# Sheet1.net
KiCad netlist of a schematic drawn in Altium Designer
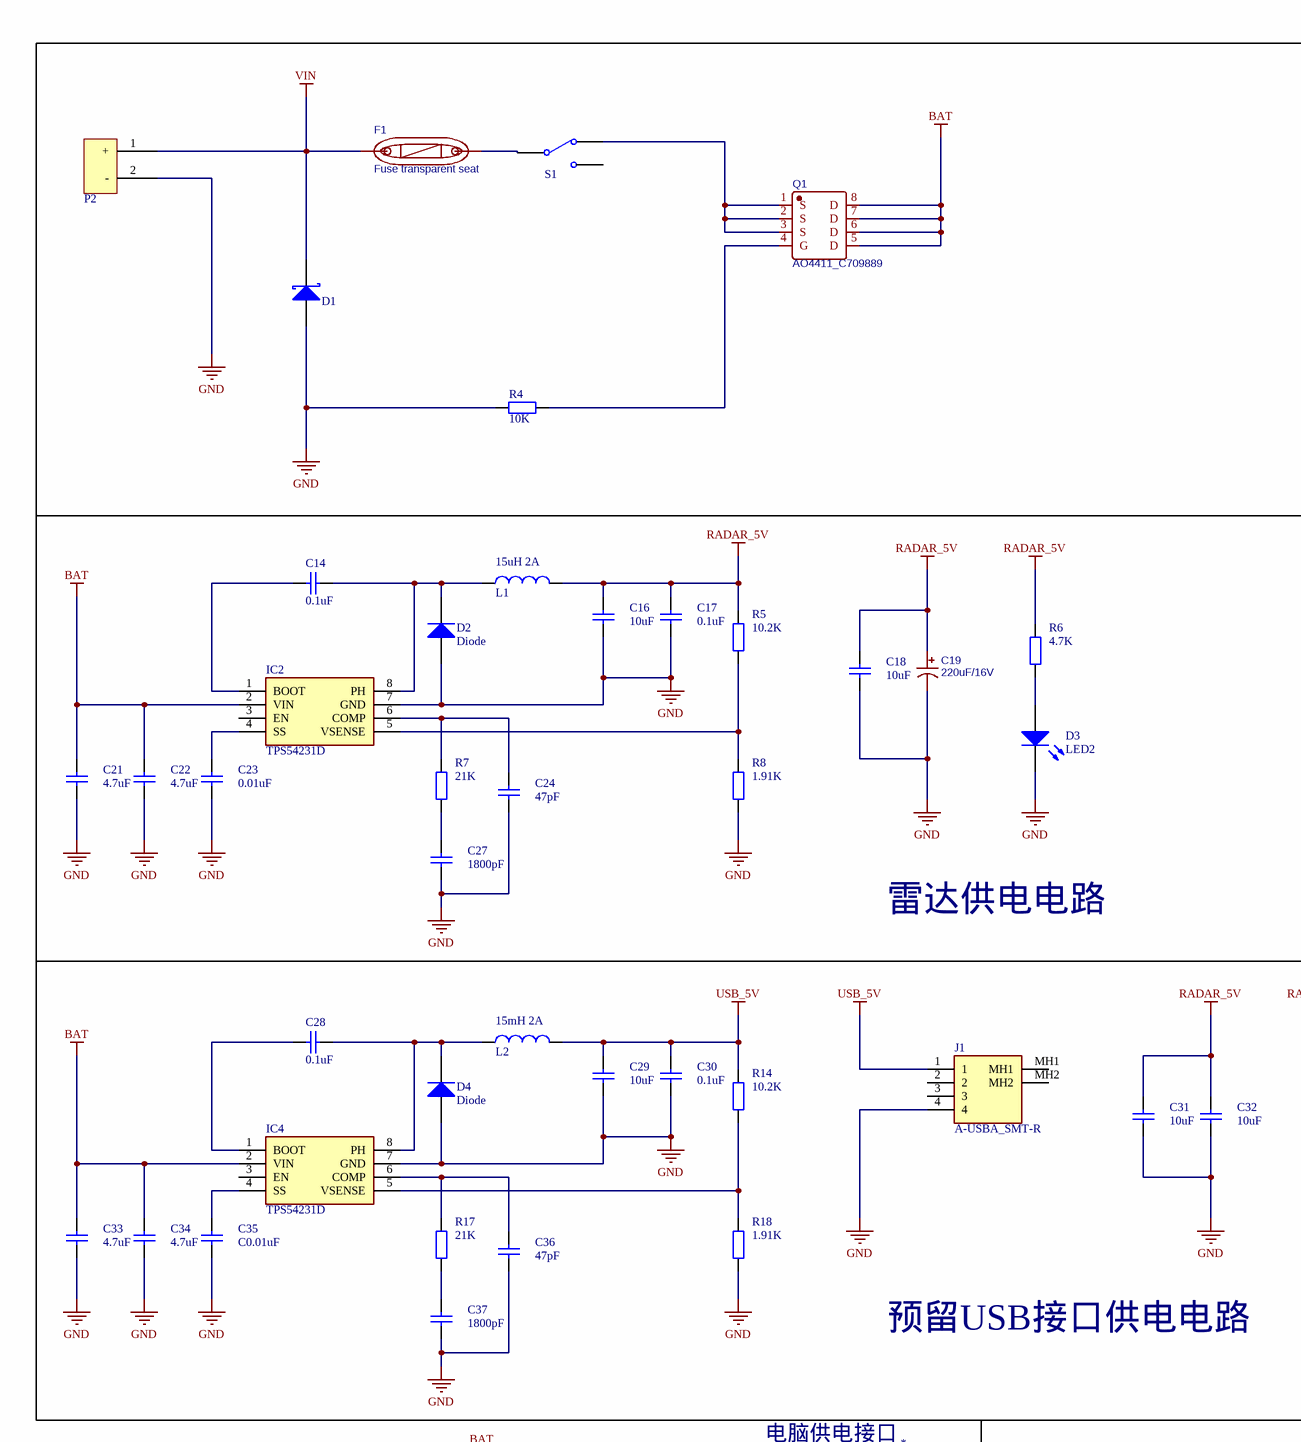
[diagram p0: Sheet1.SchDoc, top left]
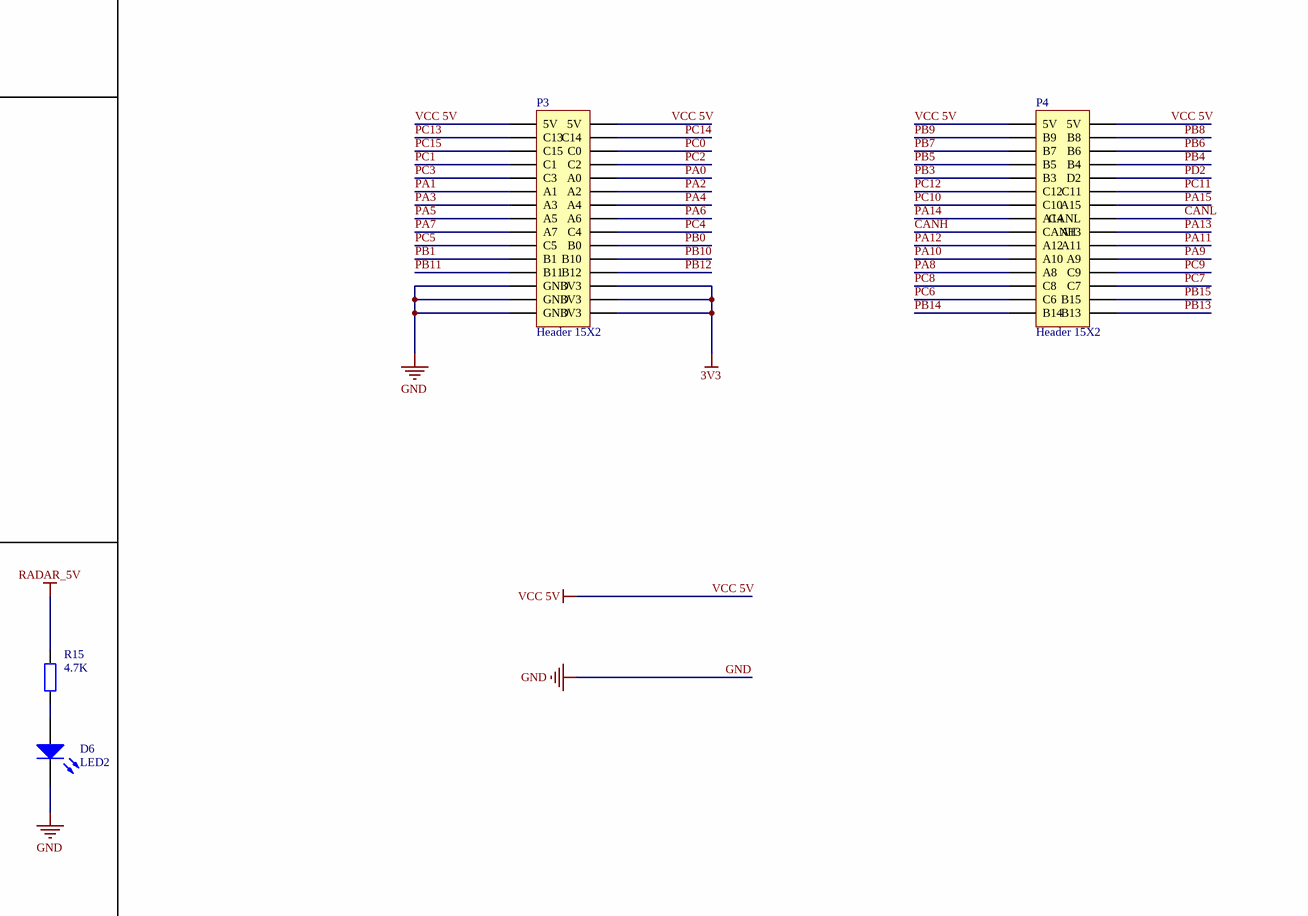
[diagram p1: Sheet1.SchDoc, top middle]
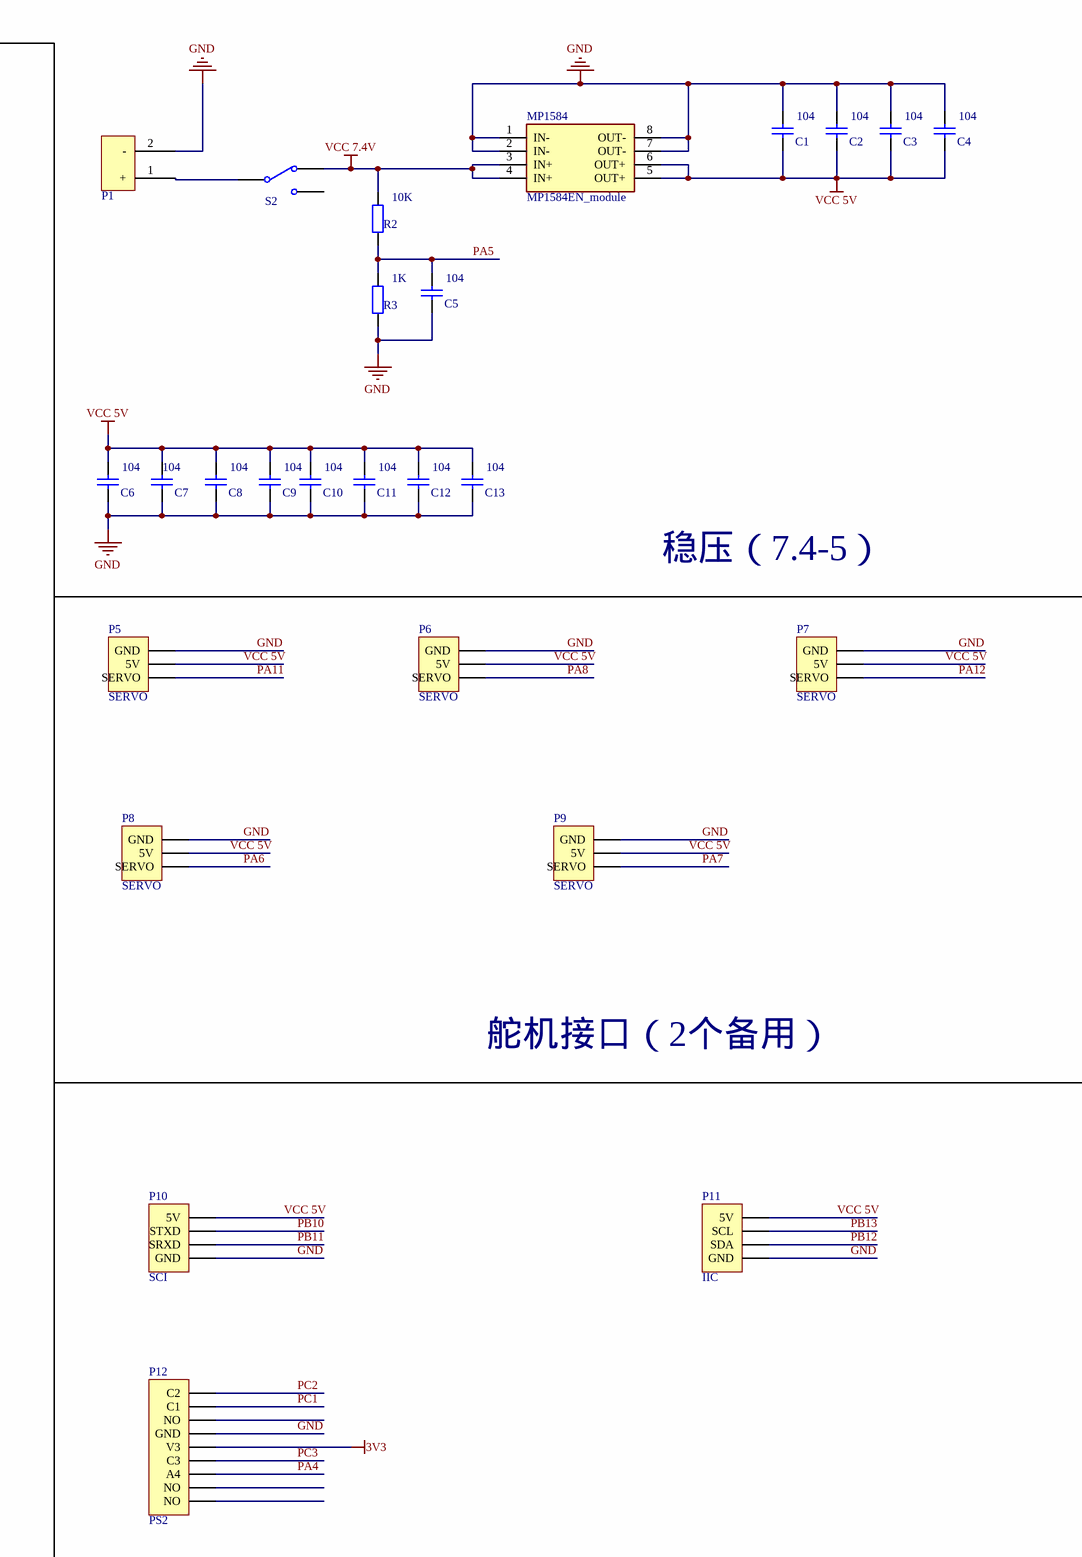
[diagram p2: Sheet1.SchDoc, top right]
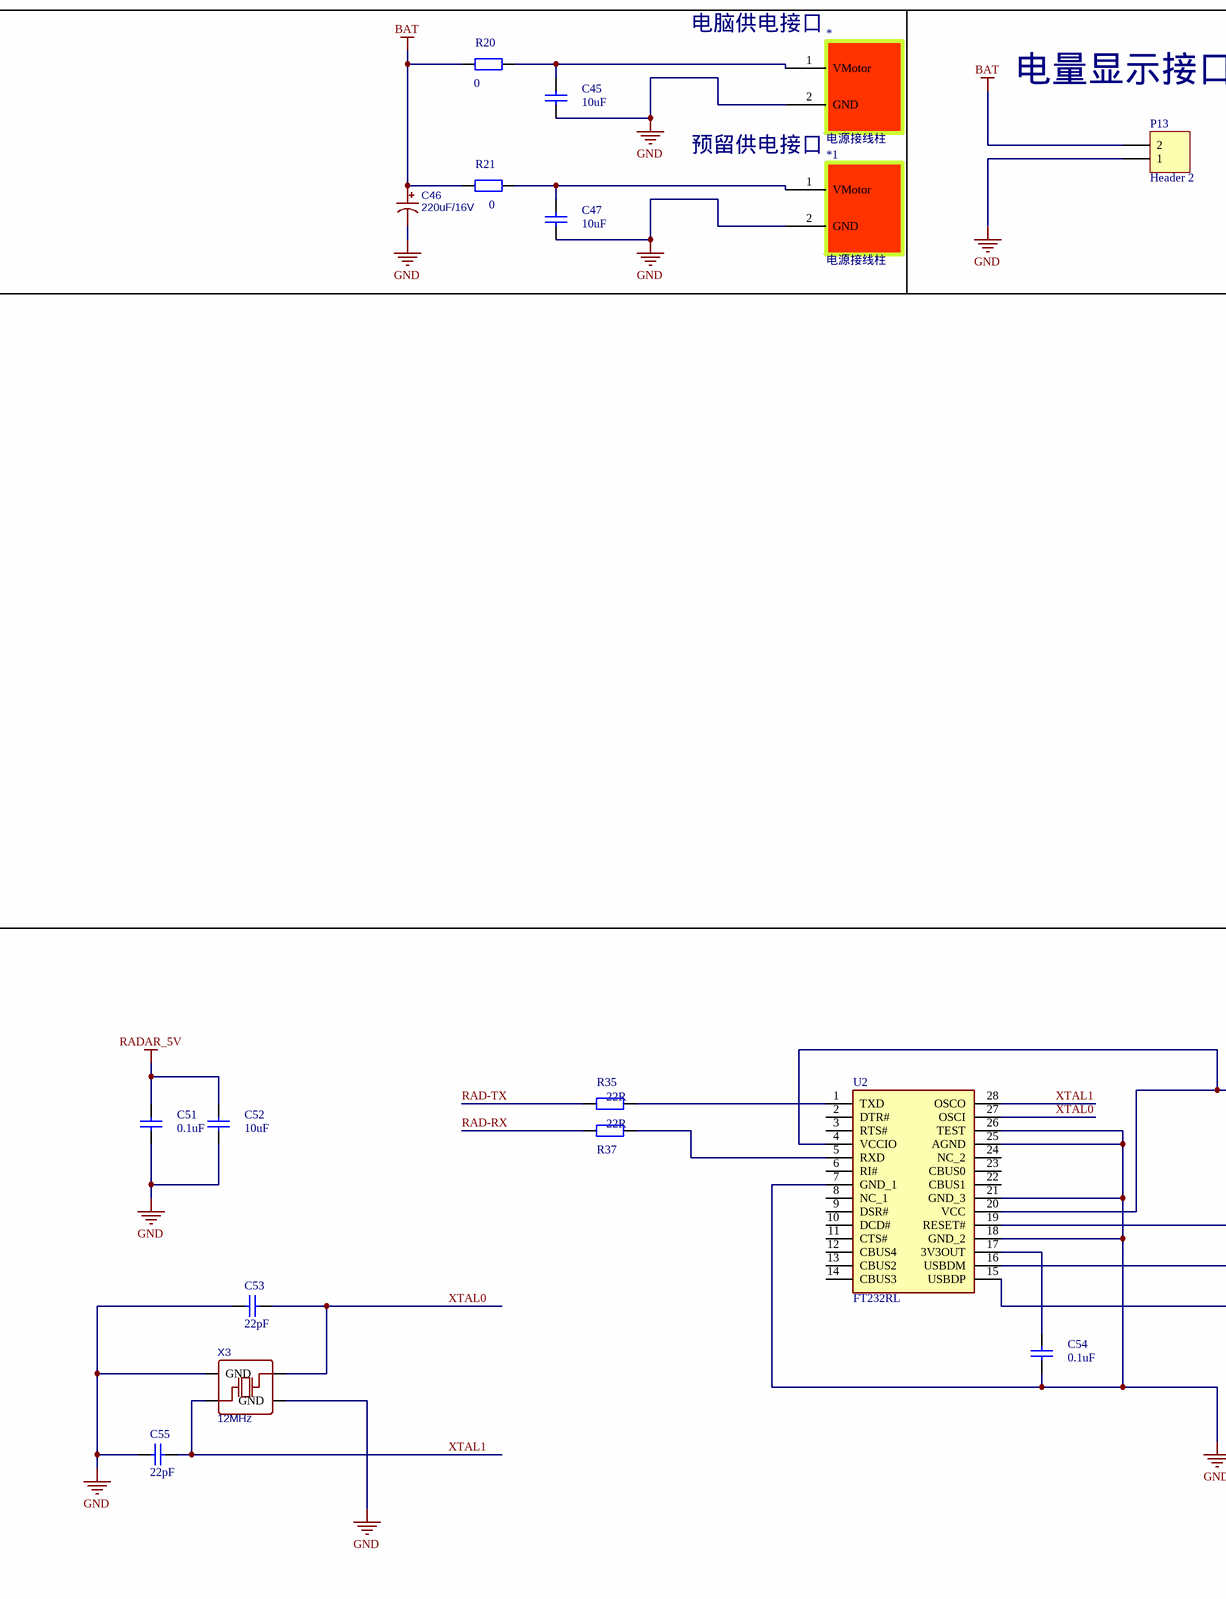
[diagram p3: Sheet1.SchDoc, bottom left]
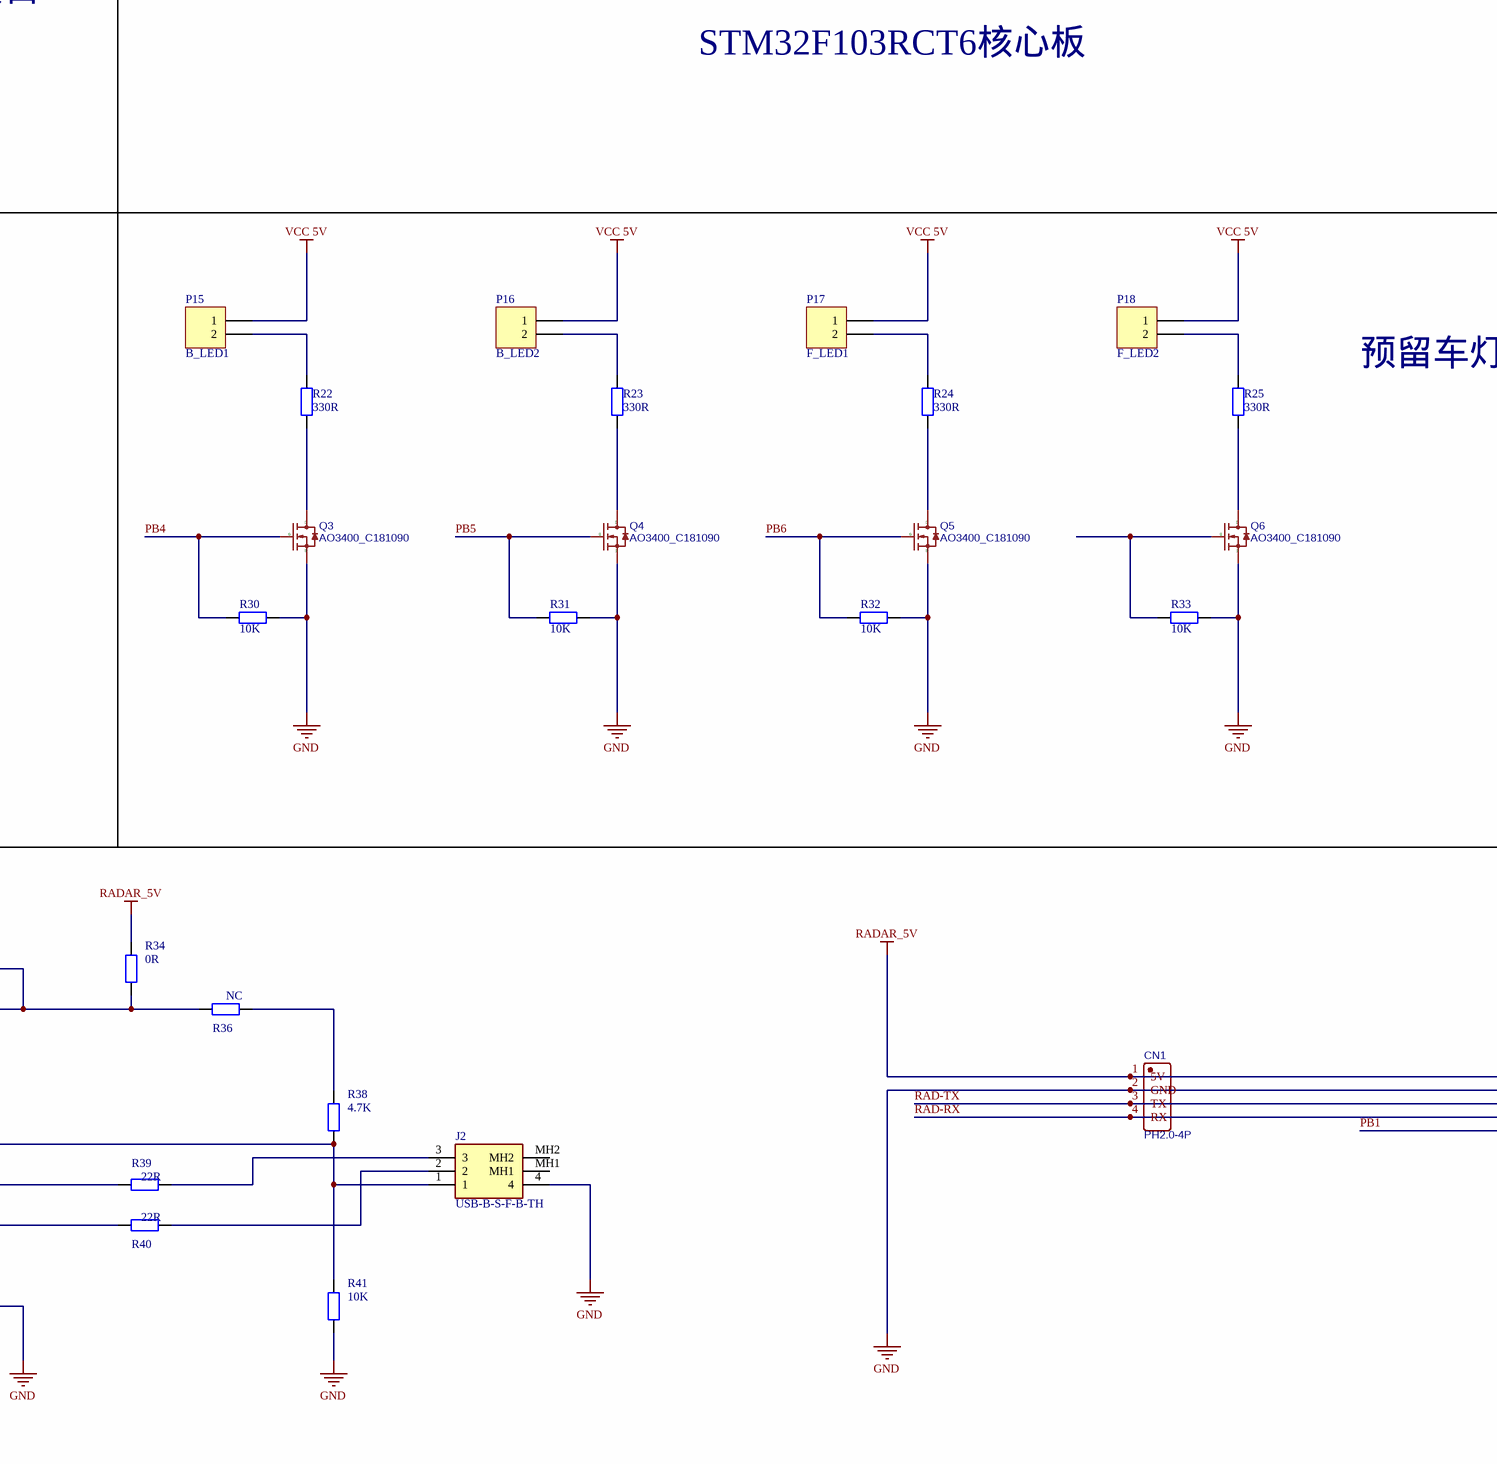
[diagram p4: Sheet1.SchDoc, bottom middle]
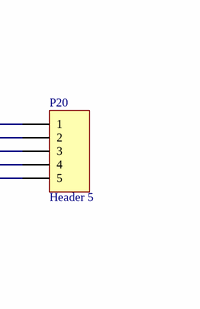
[diagram p5: Sheet1.SchDoc, bottom right]

(export (version "E")
  (design (tool "Eeschema 10.0.6"))
  (components
    (comp (ref "*") (value "电源接线柱") (footprint "接线柱") (libsource (lib "智能车元件") (part "电源接线柱")))
    (comp (ref "*1") (value "电源接线柱") (footprint "接线柱") (libsource (lib "智能车元件") (part "电源接线柱")))
    (comp (ref "C1")
      (value "104")
      (footprint "0805")
      (fields (field (name "PUBLISHER") "Altium Limited"))
      (libsource (lib "智能车元件") (part "C"))
    )
    (comp (ref "C2")
      (value "104")
      (footprint "0805")
      (fields (field (name "PUBLISHER") "Altium Limited"))
      (libsource (lib "智能车元件") (part "C"))
    )
    (comp (ref "C3")
      (value "104")
      (footprint "0805")
      (fields (field (name "PUBLISHER") "Altium Limited"))
      (libsource (lib "智能车元件") (part "C"))
    )
    (comp (ref "C4")
      (value "104")
      (footprint "0805")
      (fields (field (name "PUBLISHER") "Altium Limited"))
      (libsource (lib "智能车元件") (part "C"))
    )
    (comp (ref "C5")
      (value "104")
      (footprint "0805")
      (fields (field (name "PUBLISHER") "Altium Limited"))
      (libsource (lib "智能车元件") (part "C"))
    )
    (comp (ref "C6")
      (value "104")
      (footprint "0805")
      (fields (field (name "PUBLISHER") "Altium Limited"))
      (libsource (lib "智能车元件") (part "C"))
    )
    (comp (ref "C7")
      (value "104")
      (footprint "0805")
      (fields (field (name "PUBLISHER") "Altium Limited"))
      (libsource (lib "智能车元件") (part "C"))
    )
    (comp (ref "C8")
      (value "104")
      (footprint "0805")
      (fields (field (name "PUBLISHER") "Altium Limited"))
      (libsource (lib "智能车元件") (part "C"))
    )
    (comp (ref "C9")
      (value "104")
      (footprint "0805")
      (fields (field (name "PUBLISHER") "Altium Limited"))
      (libsource (lib "智能车元件") (part "C"))
    )
    (comp (ref "C10")
      (value "104")
      (footprint "0805")
      (fields (field (name "PUBLISHER") "Altium Limited"))
      (libsource (lib "智能车元件") (part "C"))
    )
    (comp (ref "C11")
      (value "104")
      (footprint "0805")
      (fields (field (name "PUBLISHER") "Altium Limited"))
      (libsource (lib "智能车元件") (part "C"))
    )
    (comp (ref "C12")
      (value "104")
      (footprint "0805")
      (fields (field (name "PUBLISHER") "Altium Limited"))
      (libsource (lib "智能车元件") (part "C"))
    )
    (comp (ref "C13")
      (value "104")
      (footprint "0805")
      (fields (field (name "PUBLISHER") "Altium Limited"))
      (libsource (lib "智能车元件") (part "C"))
    )
    (comp (ref "C14")
      (value "0.1uF")
      (footprint "0805")
      (fields (field (name "PUBLISHER") "Altium Limited"))
      (libsource (lib "智能车元件") (part "C"))
    )
    (comp (ref "C16")
      (value "10uF")
      (footprint "0805")
      (fields (field (name "PUBLISHER") "Altium Limited"))
      (libsource (lib "智能车元件") (part "C"))
    )
    (comp (ref "C17")
      (value "0.1uF")
      (footprint "0805")
      (fields (field (name "PUBLISHER") "Altium Limited"))
      (libsource (lib "智能车元件") (part "C"))
    )
    (comp (ref "C18")
      (value "10uF")
      (footprint "0805")
      (fields (field (name "PUBLISHER") "Altium Limited"))
      (libsource (lib "智能车元件") (part "C"))
    )
    (comp (ref "C19")
      (value "220uF/16V")
      (footprint "CAP-SMD_BD6.3-L6.6-W6.6-RD")
      (fields
        (field (name "BOM_MANUFACTURER PART") "ZV100M050E055R")
        (field (name "BOM_SUPPLIER PART") "C65228")
      )
      (libsource (lib "CAP_SMD") (part "10uF"))
    )
    (comp (ref "C21")
      (value "4.7uF")
      (footprint "0805")
      (fields (field (name "PUBLISHER") "Altium Limited"))
      (libsource (lib "智能车元件") (part "C"))
    )
    (comp (ref "C22")
      (value "4.7uF")
      (footprint "0805")
      (fields (field (name "PUBLISHER") "Altium Limited"))
      (libsource (lib "智能车元件") (part "C"))
    )
    (comp (ref "C23")
      (value "0.01uF")
      (footprint "0805")
      (fields (field (name "PUBLISHER") "Altium Limited"))
      (libsource (lib "智能车元件") (part "C"))
    )
    (comp (ref "C24")
      (value "47pF")
      (footprint "0805")
      (fields (field (name "PUBLISHER") "Altium Limited"))
      (libsource (lib "智能车元件") (part "C"))
    )
    (comp (ref "C27")
      (value "1800pF")
      (footprint "0805")
      (fields (field (name "PUBLISHER") "Altium Limited"))
      (libsource (lib "智能车元件") (part "C"))
    )
    (comp (ref "C28")
      (value "0.1uF")
      (footprint "0805")
      (fields (field (name "PUBLISHER") "Altium Limited"))
      (libsource (lib "智能车元件") (part "C"))
    )
    (comp (ref "C29")
      (value "10uF")
      (footprint "0805")
      (fields (field (name "PUBLISHER") "Altium Limited"))
      (libsource (lib "智能车元件") (part "C"))
    )
    (comp (ref "C30")
      (value "0.1uF")
      (footprint "0805")
      (fields (field (name "PUBLISHER") "Altium Limited"))
      (libsource (lib "智能车元件") (part "C"))
    )
    (comp (ref "C31")
      (value "10uF")
      (footprint "0805")
      (fields (field (name "PUBLISHER") "Altium Limited"))
      (libsource (lib "智能车元件") (part "C"))
    )
    (comp (ref "C32")
      (value "10uF")
      (footprint "0805")
      (fields (field (name "PUBLISHER") "Altium Limited"))
      (libsource (lib "智能车元件") (part "C"))
    )
    (comp (ref "C33")
      (value "4.7uF")
      (footprint "0805")
      (fields (field (name "PUBLISHER") "Altium Limited"))
      (libsource (lib "智能车元件") (part "C"))
    )
    (comp (ref "C34")
      (value "4.7uF")
      (footprint "0805")
      (fields (field (name "PUBLISHER") "Altium Limited"))
      (libsource (lib "智能车元件") (part "C"))
    )
    (comp (ref "C35")
      (value "C0.01uF")
      (footprint "0805")
      (fields (field (name "PUBLISHER") "Altium Limited"))
      (libsource (lib "智能车元件") (part "C"))
    )
    (comp (ref "C36")
      (value "47pF")
      (footprint "0805")
      (fields (field (name "PUBLISHER") "Altium Limited"))
      (libsource (lib "智能车元件") (part "C"))
    )
    (comp (ref "C37")
      (value "1800pF")
      (footprint "0805")
      (fields (field (name "PUBLISHER") "Altium Limited"))
      (libsource (lib "智能车元件") (part "C"))
    )
    (comp (ref "C45")
      (value "10uF")
      (footprint "0805")
      (fields (field (name "PUBLISHER") "Altium Limited"))
      (libsource (lib "智能车元件") (part "C"))
    )
    (comp (ref "C46")
      (value "220uF/16V")
      (footprint "CAP-SMD_BD6.3-L6.6-W6.6-RD")
      (fields
        (field (name "BOM_MANUFACTURER PART") "ZV100M050E055R")
        (field (name "BOM_SUPPLIER PART") "C65228")
      )
      (libsource (lib "CAP_SMD") (part "10uF"))
    )
    (comp (ref "C47")
      (value "10uF")
      (footprint "0805")
      (fields (field (name "PUBLISHER") "Altium Limited"))
      (libsource (lib "智能车元件") (part "C"))
    )
    (comp (ref "C51")
      (value "0.1uF")
      (footprint "0805")
      (fields (field (name "PUBLISHER") "Altium Limited"))
      (libsource (lib "智能车元件") (part "C"))
    )
    (comp (ref "C52")
      (value "10uF")
      (footprint "0805")
      (fields (field (name "PUBLISHER") "Altium Limited"))
      (libsource (lib "智能车元件") (part "C"))
    )
    (comp (ref "C53")
      (value "22pF")
      (footprint "0805")
      (fields (field (name "PUBLISHER") "Altium Limited"))
      (libsource (lib "智能车元件") (part "C"))
    )
    (comp (ref "C54")
      (value "0.1uF")
      (footprint "0805")
      (fields (field (name "PUBLISHER") "Altium Limited"))
      (libsource (lib "智能车元件") (part "C"))
    )
    (comp (ref "C55")
      (value "22pF")
      (footprint "0805")
      (fields (field (name "PUBLISHER") "Altium Limited"))
      (libsource (lib "智能车元件") (part "C"))
    )
    (comp (ref "CN1")
      (value "PH2.0-4P")
      (footprint "CONN-TH_PH2.0-4P")
      (fields (field (name "BOM_SUPPLIER PART") "C722763") (field (name "CONTRIBUTOR") "LCSC"))
      (libsource (lib "4P-2.0") (part "PH2.0-4P"))
    )
    (comp (ref "D1") (value "D-SS12") (footprint "SMA") (libsource (lib "智能车元件") (part "D-SS12")))
    (comp (ref "D2")
      (value "Diode")
      (footprint "SMC")
      (description "Default Diode")
      (fields (field (name "PUBLISHER") "Altium Limited"))
      (libsource (lib "Miscellaneous Devices") (part "Diode"))
    )
    (comp (ref "D3")
      (value "LED2")
      (footprint "3.2X1.6X1.1")
      (description "Typical RED, GREEN, YELLOW, AMBER GaAs LED")
      (fields (field (name "PUBLISHER") "Altium Limited"))
      (libsource (lib "Miscellaneous Devices") (part "LED2"))
    )
    (comp (ref "D4")
      (value "Diode")
      (footprint "SMC")
      (description "Default Diode")
      (fields (field (name "PUBLISHER") "Altium Limited"))
      (libsource (lib "Miscellaneous Devices") (part "Diode"))
    )
    (comp (ref "D6")
      (value "LED2")
      (footprint "3.2X1.6X1.1")
      (description "Typical RED, GREEN, YELLOW, AMBER GaAs LED")
      (fields (field (name "PUBLISHER") "Altium Limited"))
      (libsource (lib "Miscellaneous Devices") (part "LED2"))
    )
    (comp (ref "F1")
      (value "Fuse transparent seat")
      (footprint "FUSE-TH_L24.5-W9.8-P22.5")
      (fields (field (name "BOM_SUPPLIER PART") "C58066"))
      (libsource (lib "FUSE seat") (part "Fuse transparent seat"))
    )
    (comp (ref "IC2")
      (value "TPS54231D")
      (footprint "CAR1:SOIC127P600X175-8N")
      (description "Integrated Circuit")
      (fields (field (name "MOUSER PART NUMBER") "595-TPS54231D"))
      (libsource (lib "CAR1") (part "TPS54231D"))
    )
    (comp (ref "IC4")
      (value "TPS54231D")
      (footprint "CAR1:SOIC127P600X175-8N")
      (description "Integrated Circuit")
      (fields (field (name "MOUSER PART NUMBER") "595-TPS54231D"))
      (libsource (lib "CAR1") (part "TPS54231D"))
    )
    (comp (ref "J1")
      (value "A-USBA_SMT-R")
      (footprint "CAR1:AUSBASMTR")
      (description "Connector")
      (fields (field (name "MANUFACTURER_PART_NUMBER") "A-USBA/SMT-R"))
      (libsource (lib "CAR1") (part "A-USBA_SMT-R"))
    )
    (comp (ref "J2")
      (value "USB-B-S-F-B-TH")
      (footprint "CAR1:USBBSFBTH")
      (description "Connector")
      (fields (field (name "MOUSER PART NUMBER") "200-USBBSFBTH"))
      (libsource (lib "CAR1") (part "USB-B-S-F-B-TH"))
    )
    (comp (ref "L1") (value "15uH 2A") (footprint "L-7*7") (libsource (lib "智能车元件") (part "L")))
    (comp (ref "L2") (value "15mH 2A") (footprint "L-7*7") (libsource (lib "智能车元件") (part "L")))
    (comp (ref "MP1584")
      (value "MP1584EN_module")
      (footprint "MP1584EN_module")
      (libsource (lib "CAR1") (part "MP1584EN_module"))
    )
    (comp (ref "P1") (value "P") (footprint "T插1") (libsource (lib "") (part "CON-T插_1")))
    (comp (ref "P2") (value "P") (footprint "T插1") (libsource (lib "智能车元件") (part "CON-T插")))
    (comp (ref "P3")
      (value "Header 15X2")
      (footprint "HDR2X15")
      (description "Header, 15-Pin, Dual row")
      (fields (field (name "PUBLISHER") "Altium Limited"))
      (libsource (lib "Miscellaneous Connectors") (part "Header 15X2"))
    )
    (comp (ref "P4")
      (value "Header 15X2")
      (footprint "HDR2X15")
      (description "Header, 15-Pin, Dual row")
      (fields (field (name "PUBLISHER") "Altium Limited"))
      (libsource (lib "Miscellaneous Connectors") (part "Header 15X2"))
    )
    (comp (ref "P5")
      (value "SERVO")
      (footprint "HDR1X3")
      (description "Header, 3-Pin")
      (fields (field (name "PUBLISHER") "Altium Limited"))
      (libsource (lib "Miscellaneous Connectors") (part "Header 3"))
    )
    (comp (ref "P6")
      (value "SERVO")
      (footprint "HDR1X3")
      (description "Header, 3-Pin")
      (fields (field (name "PUBLISHER") "Altium Limited"))
      (libsource (lib "Miscellaneous Connectors") (part "Header 3"))
    )
    (comp (ref "P7")
      (value "SERVO")
      (footprint "HDR1X3")
      (description "Header, 3-Pin")
      (fields (field (name "PUBLISHER") "Altium Limited"))
      (libsource (lib "Miscellaneous Connectors") (part "Header 3"))
    )
    (comp (ref "P8")
      (value "SERVO")
      (footprint "HDR1X3")
      (description "Header, 3-Pin")
      (fields (field (name "PUBLISHER") "Altium Limited"))
      (libsource (lib "Miscellaneous Connectors") (part "Header 3"))
    )
    (comp (ref "P9")
      (value "SERVO")
      (footprint "HDR1X3")
      (description "Header, 3-Pin")
      (fields (field (name "PUBLISHER") "Altium Limited"))
      (libsource (lib "Miscellaneous Connectors") (part "Header 3"))
    )
    (comp (ref "P10")
      (value "SCI")
      (footprint "HDR1X4")
      (description "Header, 4-Pin")
      (fields (field (name "PUBLISHER") "Altium Limited"))
      (libsource (lib "Miscellaneous Connectors") (part "Header 4"))
    )
    (comp (ref "P11")
      (value "IIC")
      (footprint "HDR1X4")
      (description "Header, 4-Pin")
      (fields (field (name "PUBLISHER") "Altium Limited"))
      (libsource (lib "Miscellaneous Connectors") (part "Header 4"))
    )
    (comp (ref "P12")
      (value "PS2")
      (footprint "HDR1X9")
      (description "Header, 9-Pin")
      (fields (field (name "PUBLISHER") "Altium Limited"))
      (libsource (lib "Miscellaneous Connectors") (part "Header 9"))
    )
    (comp (ref "P13")
      (value "Header 2")
      (footprint "HDR1X2")
      (description "Header, 2-Pin")
      (fields (field (name "PUBLISHER") "Altium Limited"))
      (libsource (lib "") (part "Header 2_1"))
    )
    (comp (ref "P15")
      (value "B_LED1")
      (footprint "HDR1X2")
      (description "Header, 2-Pin")
      (fields (field (name "PUBLISHER") "Altium Limited"))
      (libsource (lib "Miscellaneous Connectors") (part "Header 2"))
    )
    (comp (ref "P16")
      (value "B_LED2")
      (footprint "HDR1X2")
      (description "Header, 2-Pin")
      (fields (field (name "PUBLISHER") "Altium Limited"))
      (libsource (lib "Miscellaneous Connectors") (part "Header 2"))
    )
    (comp (ref "P17")
      (value "F_LED1")
      (footprint "HDR1X2")
      (description "Header, 2-Pin")
      (fields (field (name "PUBLISHER") "Altium Limited"))
      (libsource (lib "Miscellaneous Connectors") (part "Header 2"))
    )
    (comp (ref "P18")
      (value "F_LED2")
      (footprint "HDR1X2")
      (description "Header, 2-Pin")
      (fields (field (name "PUBLISHER") "Altium Limited"))
      (libsource (lib "Miscellaneous Connectors") (part "Header 2"))
    )
    (comp (ref "P20")
      (value "Header 5")
      (footprint "HDR1X5")
      (description "Header, 5-Pin")
      (fields (field (name "PUBLISHER") "Altium Limited"))
      (libsource (lib "Miscellaneous Connectors") (part "Header 5"))
    )
    (comp (ref "Q1")
      (value "AO4411_C709889")
      (footprint "SO-8_L4.9-W3.9-P1.27-LS5.9-BL")
      (fields
        (field (name "BOM_SUPPLIER PART") "C709889")
        (field (name "BOM_MANUFACTURER PART") "AO4411")
        (field (name "CONTRIBUTOR") "LCSC")
      )
      (libsource (lib "AO4411") (part "AO4411_C709889"))
    )
    (comp (ref "Q3")
      (value "AO3400_C181090")
      (footprint "SOT-23-3_L2.9-W1.3-P1.90-LS2.4-BR")
      (fields
        (field (name "BOM_MANUFACTURER PART") "AO3400")
        (field (name "BOM_SUPPLIER PART") "C181090")
        (field (name "CONTRIBUTOR") "LCSC")
      )
      (libsource (lib "Free Documents") (part "AO3400_C181090"))
    )
    (comp (ref "Q4")
      (value "AO3400_C181090")
      (footprint "SOT-23-3_L2.9-W1.3-P1.90-LS2.4-BR")
      (fields
        (field (name "BOM_MANUFACTURER PART") "AO3400")
        (field (name "BOM_SUPPLIER PART") "C181090")
        (field (name "CONTRIBUTOR") "LCSC")
      )
      (libsource (lib "Free Documents") (part "AO3400_C181090"))
    )
    (comp (ref "Q5")
      (value "AO3400_C181090")
      (footprint "SOT-23-3_L2.9-W1.3-P1.90-LS2.4-BR")
      (fields
        (field (name "BOM_MANUFACTURER PART") "AO3400")
        (field (name "BOM_SUPPLIER PART") "C181090")
        (field (name "CONTRIBUTOR") "LCSC")
      )
      (libsource (lib "Free Documents") (part "AO3400_C181090"))
    )
    (comp (ref "Q6")
      (value "AO3400_C181090")
      (footprint "SOT-23-3_L2.9-W1.3-P1.90-LS2.4-BR")
      (fields
        (field (name "BOM_MANUFACTURER PART") "AO3400")
        (field (name "BOM_SUPPLIER PART") "C181090")
        (field (name "CONTRIBUTOR") "LCSC")
      )
      (libsource (lib "Free Documents") (part "AO3400_C181090"))
    )
    (comp (ref "R2") (value "10K") (footprint "0805") (libsource (lib "") (part "R_1")))
    (comp (ref "R3") (value "1K") (footprint "0805") (libsource (lib "") (part "R_1")))
    (comp (ref "R4") (value "10K") (footprint "0805") (libsource (lib "") (part "R_3")))
    (comp (ref "R5") (value "10.2K") (footprint "0805") (libsource (lib "") (part "R_1")))
    (comp (ref "R6") (value "4.7K") (footprint "0805") (libsource (lib "") (part "R_1")))
    (comp (ref "R7") (value "21K") (footprint "0805") (libsource (lib "") (part "R_1")))
    (comp (ref "R8") (value "1.91K") (footprint "0805") (libsource (lib "") (part "R_1")))
    (comp (ref "R14") (value "10.2K") (footprint "0805") (libsource (lib "") (part "R_1")))
    (comp (ref "R15") (value "4.7K") (footprint "0805") (libsource (lib "") (part "R_1")))
    (comp (ref "R17") (value "21K") (footprint "0805") (libsource (lib "") (part "R_1")))
    (comp (ref "R18") (value "1.91K") (footprint "0805") (libsource (lib "") (part "R_1")))
    (comp (ref "R20") (value "0") (footprint "0805") (libsource (lib "智能车元件") (part "R")))
    (comp (ref "R21") (value "0") (footprint "0805") (libsource (lib "智能车元件") (part "R")))
    (comp (ref "R22") (value "330R") (footprint "0805") (libsource (lib "") (part "R_2")))
    (comp (ref "R23") (value "330R") (footprint "0805") (libsource (lib "") (part "R_2")))
    (comp (ref "R24") (value "330R") (footprint "0805") (libsource (lib "") (part "R_2")))
    (comp (ref "R25") (value "330R") (footprint "0805") (libsource (lib "") (part "R_2")))
    (comp (ref "R30") (value "10K") (footprint "0805") (libsource (lib "智能车元件") (part "R")))
    (comp (ref "R31") (value "10K") (footprint "0805") (libsource (lib "智能车元件") (part "R")))
    (comp (ref "R32") (value "10K") (footprint "0805") (libsource (lib "智能车元件") (part "R")))
    (comp (ref "R33") (value "10K") (footprint "0805") (libsource (lib "智能车元件") (part "R")))
    (comp (ref "R34") (value "0R") (footprint "0805") (libsource (lib "") (part "R_1")))
    (comp (ref "R35") (value "22R") (footprint "0805") (libsource (lib "智能车元件") (part "R")))
    (comp (ref "R36") (value "NC") (footprint "0805") (libsource (lib "智能车元件") (part "R")))
    (comp (ref "R37") (value "22R") (footprint "0805") (libsource (lib "智能车元件") (part "R")))
    (comp (ref "R38") (value "4.7K") (footprint "0805") (libsource (lib "") (part "R_1")))
    (comp (ref "R39") (value "22R") (footprint "0805") (libsource (lib "智能车元件") (part "R")))
    (comp (ref "R40") (value "22R") (footprint "0805") (libsource (lib "智能车元件") (part "R")))
    (comp (ref "R41") (value "10K") (footprint "0805") (libsource (lib "") (part "R_1")))
    (comp (ref "S1") (value "SWITCH") (footprint "纽子开关") (libsource (lib "智能车元件") (part "SW-钮子开关")))
    (comp (ref "S2") (value "SWITCH") (footprint "纽子开关") (libsource (lib "智能车元件") (part "SW-钮子开关")))
    (comp (ref "U2")
      (value "FT232RL")
      (footprint "CAR1:SOP65P778X200-28N")
      (description "Integrated Circuit")
      (libsource (lib "CAR1") (part "FT232RL"))
    )
    (comp (ref "X3")
      (value "12MHz")
      (footprint "OSC-SMD_4P-L3.2-W2.5-BL")
      (fields
        (field (name "BOM_SUPPLIER PART") "C258939")
        (field (name "BOM_MANUFACTURER PART") "M12000J134")
        (field (name "CONTRIBUTOR") "LCSC")
      )
      (libsource (lib "Free Documents") (part "12MHz"))
    )
  )
  (nets
    (net (code "1") (name "/CANH") (class "Default")
      (node (ref "P4") (pin "17") (pinfunction "A7_17") (pintype "passive"))
    )
    (net (code "2") (name "/CANL") (class "Default")
      (node (ref "P4") (pin "16") (pinfunction "A6_16") (pintype "passive"))
    )
    (net (code "3") (name "/PA0") (class "Default")
      (node (ref "P3") (pin "10") (pinfunction "A0_10") (pintype "passive"))
    )
    (net (code "4") (name "/PA1") (class "Default")
      (node (ref "P3") (pin "11") (pinfunction "A1_11") (pintype "passive"))
    )
    (net (code "5") (name "/PA2") (class "Default")
      (node (ref "P3") (pin "12") (pinfunction "A2_12") (pintype "passive"))
    )
    (net (code "6") (name "/PA3") (class "Default")
      (node (ref "P3") (pin "13") (pinfunction "A3_13") (pintype "passive"))
    )
    (net (code "7") (name "/PA4") (class "Default")
      (node (ref "P12") (pin "7") (pinfunction "A4_7") (pintype "passive"))
      (node (ref "P3") (pin "14") (pinfunction "A4_14") (pintype "passive"))
    )
    (net (code "8") (name "/PA5") (class "Default")
      (node (ref "C5") (pin "2") (pinfunction "2_2") (pintype "passive"))
      (node (ref "P3") (pin "15") (pinfunction "A5_15") (pintype "passive"))
      (node (ref "R2") (pin "1") (pinfunction "1_1") (pintype "passive"))
      (node (ref "R3") (pin "2") (pinfunction "2_2") (pintype "passive"))
    )
    (net (code "9") (name "/PA6") (class "Default")
      (node (ref "P3") (pin "16") (pinfunction "A6_16") (pintype "passive"))
      (node (ref "P8") (pin "3") (pinfunction "SERVO_3") (pintype "passive"))
    )
    (net (code "10") (name "/PA7") (class "Default")
      (node (ref "P3") (pin "17") (pinfunction "A7_17") (pintype "passive"))
      (node (ref "P9") (pin "3") (pinfunction "SERVO_3") (pintype "passive"))
    )
    (net (code "11") (name "/PA8") (class "Default")
      (node (ref "P4") (pin "23") (pinfunction "B11_23") (pintype "passive"))
      (node (ref "P6") (pin "3") (pinfunction "SERVO_3") (pintype "passive"))
    )
    (net (code "12") (name "/PA9") (class "Default")
      (node (ref "P4") (pin "22") (pinfunction "B10_22") (pintype "passive"))
    )
    (net (code "13") (name "/PA10") (class "Default")
      (node (ref "P4") (pin "21") (pinfunction "B1_21") (pintype "passive"))
    )
    (net (code "14") (name "/PA11") (class "Default")
      (node (ref "P4") (pin "20") (pinfunction "B0_20") (pintype "passive"))
      (node (ref "P5") (pin "3") (pinfunction "SERVO_3") (pintype "passive"))
    )
    (net (code "15") (name "/PA12") (class "Default")
      (node (ref "P4") (pin "19") (pinfunction "C5_19") (pintype "passive"))
      (node (ref "P7") (pin "3") (pinfunction "SERVO_3") (pintype "passive"))
    )
    (net (code "16") (name "/PA13") (class "Default")
      (node (ref "P4") (pin "18") (pinfunction "C4_18") (pintype "passive"))
    )
    (net (code "17") (name "/PA14") (class "Default")
      (node (ref "P4") (pin "15") (pinfunction "A5_15") (pintype "passive"))
    )
    (net (code "18") (name "/PA15") (class "Default")
      (node (ref "P4") (pin "14") (pinfunction "A4_14") (pintype "passive"))
    )
    (net (code "19") (name "/PB0") (class "Default")
      (node (ref "P3") (pin "20") (pinfunction "B0_20") (pintype "passive"))
    )
    (net (code "20") (name "/PB1") (class "Default")
      (node (ref "P20") (pin "5") (pinfunction "5_5") (pintype "passive"))
      (node (ref "P3") (pin "21") (pinfunction "B1_21") (pintype "passive"))
    )
    (net (code "21") (name "/PB3") (class "Default")
      (node (ref "P4") (pin "9") (pinfunction "C3_9") (pintype "passive"))
    )
    (net (code "22") (name "/PB4") (class "Default")
      (node (ref "P4") (pin "8") (pinfunction "C2_8") (pintype "passive"))
      (node (ref "Q3") (pin "1") (pinfunction "G_1") (pintype "passive"))
      (node (ref "R30") (pin "1") (pinfunction "1_1") (pintype "passive"))
    )
    (net (code "23") (name "/PB5") (class "Default")
      (node (ref "P4") (pin "7") (pinfunction "C1_7") (pintype "passive"))
      (node (ref "Q4") (pin "1") (pinfunction "G_1") (pintype "passive"))
      (node (ref "R31") (pin "1") (pinfunction "1_1") (pintype "passive"))
    )
    (net (code "24") (name "/PB6") (class "Default")
      (node (ref "P4") (pin "6") (pinfunction "C0_6") (pintype "passive"))
      (node (ref "Q5") (pin "1") (pinfunction "G_1") (pintype "passive"))
      (node (ref "R32") (pin "1") (pinfunction "1_1") (pintype "passive"))
    )
    (net (code "25") (name "/PB7") (class "Default")
      (node (ref "P4") (pin "5") (pinfunction "C15_5") (pintype "passive"))
    )
    (net (code "26") (name "/PB8") (class "Default")
      (node (ref "P4") (pin "4") (pinfunction "C14_4") (pintype "passive"))
    )
    (net (code "27") (name "/PB9") (class "Default")
      (node (ref "P4") (pin "3") (pinfunction "C13_3") (pintype "passive"))
    )
    (net (code "28") (name "/PB10") (class "Default")
      (node (ref "P10") (pin "2") (pinfunction "SCL_2") (pintype "passive"))
      (node (ref "P3") (pin "22") (pinfunction "B10_22") (pintype "passive"))
    )
    (net (code "29") (name "/PB11") (class "Default")
      (node (ref "P10") (pin "3") (pinfunction "SDA_3") (pintype "passive"))
      (node (ref "P3") (pin "23") (pinfunction "B11_23") (pintype "passive"))
    )
    (net (code "30") (name "/PB12") (class "Default")
      (node (ref "P11") (pin "3") (pinfunction "SDA_3") (pintype "passive"))
      (node (ref "P3") (pin "24") (pinfunction "B12_24") (pintype "passive"))
    )
    (net (code "31") (name "/PB13") (class "Default")
      (node (ref "P11") (pin "2") (pinfunction "SCL_2") (pintype "passive"))
      (node (ref "P4") (pin "30") (pinfunction "3V3_30") (pintype "passive"))
    )
    (net (code "32") (name "/PB14") (class "Default")
      (node (ref "P4") (pin "29") (pinfunction "GND_29") (pintype "passive"))
    )
    (net (code "33") (name "/PB15") (class "Default")
      (node (ref "P4") (pin "28") (pinfunction "3V3_28") (pintype "passive"))
    )
    (net (code "34") (name "/PC0") (class "Default")
      (node (ref "P3") (pin "6") (pinfunction "C0_6") (pintype "passive"))
    )
    (net (code "35") (name "/PC1") (class "Default")
      (node (ref "P12") (pin "2") (pinfunction "C1_2") (pintype "passive"))
      (node (ref "P3") (pin "7") (pinfunction "C1_7") (pintype "passive"))
    )
    (net (code "36") (name "/PC2") (class "Default")
      (node (ref "P12") (pin "1") (pinfunction "C2_1") (pintype "passive"))
      (node (ref "P3") (pin "8") (pinfunction "C2_8") (pintype "passive"))
    )
    (net (code "37") (name "/PC3") (class "Default")
      (node (ref "P12") (pin "6") (pinfunction "C3_6") (pintype "passive"))
      (node (ref "P3") (pin "9") (pinfunction "C3_9") (pintype "passive"))
    )
    (net (code "38") (name "/PC4") (class "Default")
      (node (ref "P3") (pin "18") (pinfunction "C4_18") (pintype "passive"))
    )
    (net (code "39") (name "/PC5") (class "Default")
      (node (ref "P3") (pin "19") (pinfunction "C5_19") (pintype "passive"))
    )
    (net (code "40") (name "/PC6") (class "Default")
      (node (ref "P4") (pin "27") (pinfunction "GND_27") (pintype "passive"))
    )
    (net (code "41") (name "/PC7") (class "Default")
      (node (ref "P4") (pin "26") (pinfunction "3V3_26") (pintype "passive"))
    )
    (net (code "42") (name "/PC8") (class "Default")
      (node (ref "P4") (pin "25") (pinfunction "GND_25") (pintype "passive"))
    )
    (net (code "43") (name "/PC9") (class "Default")
      (node (ref "P4") (pin "24") (pinfunction "B12_24") (pintype "passive"))
    )
    (net (code "44") (name "/PC10") (class "Default")
      (node (ref "P4") (pin "13") (pinfunction "A3_13") (pintype "passive"))
    )
    (net (code "45") (name "/PC11") (class "Default")
      (node (ref "P4") (pin "12") (pinfunction "A2_12") (pintype "passive"))
    )
    (net (code "46") (name "/PC12") (class "Default")
      (node (ref "P4") (pin "11") (pinfunction "A1_11") (pintype "passive"))
    )
    (net (code "47") (name "/PC13") (class "Default")
      (node (ref "P3") (pin "3") (pinfunction "C13_3") (pintype "passive"))
    )
    (net (code "48") (name "/PC14") (class "Default")
      (node (ref "P3") (pin "4") (pinfunction "C14_4") (pintype "passive"))
    )
    (net (code "49") (name "/PC15") (class "Default")
      (node (ref "P3") (pin "5") (pinfunction "C15_5") (pintype "passive"))
    )
    (net (code "50") (name "/PD2") (class "Default")
      (node (ref "P4") (pin "10") (pinfunction "A0_10") (pintype "passive"))
    )
    (net (code "51") (name "/RAD-RX") (class "Default")
      (node (ref "CN1") (pin "4") (pinfunction "RX_4") (pintype "passive"))
      (node (ref "P20") (pin "4") (pinfunction "4_4") (pintype "passive"))
      (node (ref "R37") (pin "1") (pinfunction "1_1") (pintype "passive"))
    )
    (net (code "52") (name "/RAD-TX") (class "Default")
      (node (ref "CN1") (pin "3") (pinfunction "TX_3") (pintype "passive"))
      (node (ref "P20") (pin "3") (pinfunction "3_3") (pintype "passive"))
      (node (ref "R35") (pin "1") (pinfunction "1_1") (pintype "passive"))
    )
    (net (code "53") (name "/XTAL0") (class "Default")
      (node (ref "C53") (pin "1") (pinfunction "1_1") (pintype "passive"))
      (node (ref "U2") (pin "27") (pinfunction "OSCI_27") (pintype "passive"))
      (node (ref "X3") (pin "3") (pinfunction "OSC2_3") (pintype "passive"))
    )
    (net (code "54") (name "/XTAL1") (class "Default")
      (node (ref "C55") (pin "1") (pinfunction "1_1") (pintype "passive"))
      (node (ref "U2") (pin "28") (pinfunction "OSCO_28") (pintype "passive"))
      (node (ref "X3") (pin "1") (pinfunction "OSC1_1") (pintype "passive"))
    )
    (net (code "55") (name "3V3") (class "Default")
      (node (ref "P12") (pin "5") (pinfunction "V3_5") (pintype "passive"))
      (node (ref "P3") (pin "26") (pinfunction "3V3_26") (pintype "passive"))
      (node (ref "P3") (pin "28") (pinfunction "3V3_28") (pintype "passive"))
      (node (ref "P3") (pin "30") (pinfunction "3V3_30") (pintype "passive"))
    )
    (net (code "56") (name "BAT") (class "Default")
      (node (ref "C21") (pin "2") (pinfunction "2_2") (pintype "passive"))
      (node (ref "C22") (pin "2") (pinfunction "2_2") (pintype "passive"))
      (node (ref "C33") (pin "2") (pinfunction "2_2") (pintype "passive"))
      (node (ref "C34") (pin "2") (pinfunction "2_2") (pintype "passive"))
      (node (ref "C46") (pin "1") (pinfunction "1_1") (pintype "passive"))
      (node (ref "IC2") (pin "2") (pinfunction "VIN_2") (pintype "passive"))
      (node (ref "IC4") (pin "2") (pinfunction "VIN_2") (pintype "passive"))
      (node (ref "P13") (pin "2") (pinfunction "2_2") (pintype "passive"))
      (node (ref "Q1") (pin "5") (pinfunction "D_5") (pintype "passive"))
      (node (ref "Q1") (pin "6") (pinfunction "D_6") (pintype "passive"))
      (node (ref "Q1") (pin "7") (pinfunction "D_7") (pintype "passive"))
      (node (ref "Q1") (pin "8") (pinfunction "D_8") (pintype "passive"))
      (node (ref "R20") (pin "1") (pinfunction "1_1") (pintype "passive"))
      (node (ref "R21") (pin "1") (pinfunction "1_1") (pintype "passive"))
    )
    (net (code "57") (name "GND") (class "Default")
      (node (ref "*") (pin "2") (pinfunction "GND_2") (pintype "passive"))
      (node (ref "*1") (pin "2") (pinfunction "GND_2") (pintype "passive"))
      (node (ref "C1") (pin "2") (pinfunction "2_2") (pintype "passive"))
      (node (ref "C10") (pin "1") (pinfunction "1_1") (pintype "passive"))
      (node (ref "C11") (pin "1") (pinfunction "1_1") (pintype "passive"))
      (node (ref "C12") (pin "1") (pinfunction "1_1") (pintype "passive"))
      (node (ref "C13") (pin "1") (pinfunction "1_1") (pintype "passive"))
      (node (ref "C16") (pin "1") (pinfunction "1_1") (pintype "passive"))
      (node (ref "C17") (pin "1") (pinfunction "1_1") (pintype "passive"))
      (node (ref "C18") (pin "1") (pinfunction "1_1") (pintype "passive"))
      (node (ref "C19") (pin "2") (pinfunction "2_2") (pintype "passive"))
      (node (ref "C2") (pin "2") (pinfunction "2_2") (pintype "passive"))
      (node (ref "C21") (pin "1") (pinfunction "1_1") (pintype "passive"))
      (node (ref "C22") (pin "1") (pinfunction "1_1") (pintype "passive"))
      (node (ref "C23") (pin "1") (pinfunction "1_1") (pintype "passive"))
      (node (ref "C24") (pin "1") (pinfunction "1_1") (pintype "passive"))
      (node (ref "C27") (pin "1") (pinfunction "1_1") (pintype "passive"))
      (node (ref "C29") (pin "1") (pinfunction "1_1") (pintype "passive"))
      (node (ref "C3") (pin "2") (pinfunction "2_2") (pintype "passive"))
      (node (ref "C30") (pin "1") (pinfunction "1_1") (pintype "passive"))
      (node (ref "C31") (pin "1") (pinfunction "1_1") (pintype "passive"))
      (node (ref "C32") (pin "1") (pinfunction "1_1") (pintype "passive"))
      (node (ref "C33") (pin "1") (pinfunction "1_1") (pintype "passive"))
      (node (ref "C34") (pin "1") (pinfunction "1_1") (pintype "passive"))
      (node (ref "C35") (pin "1") (pinfunction "1_1") (pintype "passive"))
      (node (ref "C36") (pin "1") (pinfunction "1_1") (pintype "passive"))
      (node (ref "C37") (pin "1") (pinfunction "1_1") (pintype "passive"))
      (node (ref "C4") (pin "2") (pinfunction "2_2") (pintype "passive"))
      (node (ref "C45") (pin "1") (pinfunction "1_1") (pintype "passive"))
      (node (ref "C46") (pin "2") (pinfunction "2_2") (pintype "passive"))
      (node (ref "C47") (pin "1") (pinfunction "1_1") (pintype "passive"))
      (node (ref "C5") (pin "1") (pinfunction "1_1") (pintype "passive"))
      (node (ref "C51") (pin "1") (pinfunction "1_1") (pintype "passive"))
      (node (ref "C52") (pin "1") (pinfunction "1_1") (pintype "passive"))
      (node (ref "C53") (pin "2") (pinfunction "2_2") (pintype "passive"))
      (node (ref "C54") (pin "1") (pinfunction "1_1") (pintype "passive"))
      (node (ref "C55") (pin "2") (pinfunction "2_2") (pintype "passive"))
      (node (ref "C6") (pin "1") (pinfunction "1_1") (pintype "passive"))
      (node (ref "C7") (pin "1") (pinfunction "1_1") (pintype "passive"))
      (node (ref "C8") (pin "1") (pinfunction "1_1") (pintype "passive"))
      (node (ref "C9") (pin "1") (pinfunction "1_1") (pintype "passive"))
      (node (ref "CN1") (pin "2") (pinfunction "GND_2") (pintype "passive"))
      (node (ref "D1") (pin "1") (pinfunction "A_1") (pintype "passive"))
      (node (ref "D2") (pin "1") (pinfunction "A_1") (pintype "passive"))
      (node (ref "D3") (pin "2") (pinfunction "K_2") (pintype "passive"))
      (node (ref "D4") (pin "1") (pinfunction "A_1") (pintype "passive"))
      (node (ref "D6") (pin "2") (pinfunction "K_2") (pintype "passive"))
      (node (ref "IC2") (pin "7") (pinfunction "GND_7") (pintype "passive"))
      (node (ref "IC4") (pin "7") (pinfunction "GND_7") (pintype "passive"))
      (node (ref "J1") (pin "4") (pinfunction "4_4") (pintype "passive"))
      (node (ref "J2") (pin "4") (pinfunction "4_4") (pintype "passive"))
      (node (ref "MP1584") (pin "1") (pinfunction "IN-_1") (pintype "passive"))
      (node (ref "MP1584") (pin "2") (pinfunction "IN-_2") (pintype "passive"))
      (node (ref "MP1584") (pin "7") (pinfunction "OUT-_7") (pintype "passive"))
      (node (ref "MP1584") (pin "8") (pinfunction "OUT-_8") (pintype "passive"))
      (node (ref "P1") (pin "2") (pinfunction "-_2") (pintype "passive"))
      (node (ref "P10") (pin "4") (pinfunction "GND_4") (pintype "passive"))
      (node (ref "P11") (pin "4") (pinfunction "GND_4") (pintype "passive"))
      (node (ref "P12") (pin "4") (pinfunction "GND_4") (pintype "passive"))
      (node (ref "P13") (pin "1") (pinfunction "1_1") (pintype "passive"))
      (node (ref "P2") (pin "2") (pinfunction "-_2") (pintype "passive"))
      (node (ref "P20") (pin "2") (pinfunction "2_2") (pintype "passive"))
      (node (ref "P3") (pin "25") (pinfunction "GND_25") (pintype "passive"))
      (node (ref "P3") (pin "27") (pinfunction "GND_27") (pintype "passive"))
      (node (ref "P3") (pin "29") (pinfunction "GND_29") (pintype "passive"))
      (node (ref "P5") (pin "1") (pinfunction "GND_1") (pintype "passive"))
      (node (ref "P6") (pin "1") (pinfunction "GND_1") (pintype "passive"))
      (node (ref "P7") (pin "1") (pinfunction "GND_1") (pintype "passive"))
      (node (ref "P8") (pin "1") (pinfunction "GND_1") (pintype "passive"))
      (node (ref "P9") (pin "1") (pinfunction "GND_1") (pintype "passive"))
      (node (ref "Q3") (pin "2") (pinfunction "S_2") (pintype "passive"))
      (node (ref "Q4") (pin "2") (pinfunction "S_2") (pintype "passive"))
      (node (ref "Q5") (pin "2") (pinfunction "S_2") (pintype "passive"))
      (node (ref "Q6") (pin "2") (pinfunction "S_2") (pintype "passive"))
      (node (ref "R18") (pin "1") (pinfunction "1_1") (pintype "passive"))
      (node (ref "R3") (pin "1") (pinfunction "1_1") (pintype "passive"))
      (node (ref "R30") (pin "2") (pinfunction "2_2") (pintype "passive"))
      (node (ref "R31") (pin "2") (pinfunction "2_2") (pintype "passive"))
      (node (ref "R32") (pin "2") (pinfunction "2_2") (pintype "passive"))
      (node (ref "R33") (pin "2") (pinfunction "2_2") (pintype "passive"))
      (node (ref "R4") (pin "2") (pinfunction "2_2") (pintype "passive"))
      (node (ref "R41") (pin "1") (pinfunction "1_1") (pintype "passive"))
      (node (ref "R8") (pin "1") (pinfunction "1_1") (pintype "passive"))
      (node (ref "U2") (pin "18") (pinfunction "GND_2_18") (pintype "passive"))
      (node (ref "U2") (pin "21") (pinfunction "GND_3_21") (pintype "passive"))
      (node (ref "U2") (pin "25") (pinfunction "AGND_25") (pintype "passive"))
      (node (ref "U2") (pin "26") (pinfunction "TEST_26") (pintype "passive"))
      (node (ref "U2") (pin "7") (pinfunction "GND_1_7") (pintype "passive"))
      (node (ref "X3") (pin "2") (pinfunction "GND_2") (pintype "passive"))
      (node (ref "X3") (pin "4") (pinfunction "GND_4") (pintype "passive"))
    )
    (net (code "58") (name "Net-(*-VMotor)") (class "Default")
      (node (ref "*") (pin "1") (pinfunction "VMotor_1") (pintype "passive"))
      (node (ref "C45") (pin "2") (pinfunction "2_2") (pintype "passive"))
      (node (ref "R20") (pin "2") (pinfunction "2_2") (pintype "passive"))
    )
    (net (code "59") (name "Net-(*1-VMotor)") (class "Default")
      (node (ref "*1") (pin "1") (pinfunction "VMotor_1") (pintype "passive"))
      (node (ref "C47") (pin "2") (pinfunction "2_2") (pintype "passive"))
      (node (ref "R21") (pin "2") (pinfunction "2_2") (pintype "passive"))
    )
    (net (code "60") (name "Net-(C27-Pad2)") (class "Default")
      (node (ref "C27") (pin "2") (pinfunction "2_2") (pintype "passive"))
      (node (ref "R7") (pin "1") (pinfunction "1_1") (pintype "passive"))
    )
    (net (code "61") (name "Net-(C37-Pad2)") (class "Default")
      (node (ref "C37") (pin "2") (pinfunction "2_2") (pintype "passive"))
      (node (ref "R17") (pin "1") (pinfunction "1_1") (pintype "passive"))
    )
    (net (code "62") (name "Net-(D2-K)") (class "Default")
      (node (ref "C14") (pin "1") (pinfunction "1_1") (pintype "passive"))
      (node (ref "D2") (pin "2") (pinfunction "K_2") (pintype "passive"))
      (node (ref "IC2") (pin "8") (pinfunction "PH_8") (pintype "passive"))
      (node (ref "L1") (pin "1") (pinfunction "1_1") (pintype "passive"))
    )
    (net (code "63") (name "Net-(D3-A)") (class "Default")
      (node (ref "D3") (pin "1") (pinfunction "A_1") (pintype "passive"))
      (node (ref "R6") (pin "1") (pinfunction "1_1") (pintype "passive"))
    )
    (net (code "64") (name "Net-(D4-K)") (class "Default")
      (node (ref "C28") (pin "1") (pinfunction "1_1") (pintype "passive"))
      (node (ref "D4") (pin "2") (pinfunction "K_2") (pintype "passive"))
      (node (ref "IC4") (pin "8") (pinfunction "PH_8") (pintype "passive"))
      (node (ref "L2") (pin "1") (pinfunction "1_1") (pintype "passive"))
    )
    (net (code "65") (name "Net-(D6-A)") (class "Default")
      (node (ref "D6") (pin "1") (pinfunction "A_1") (pintype "passive"))
      (node (ref "R15") (pin "1") (pinfunction "1_1") (pintype "passive"))
    )
    (net (code "66") (name "Net-(IC2-BOOT)") (class "Default")
      (node (ref "C14") (pin "2") (pinfunction "2_2") (pintype "passive"))
      (node (ref "IC2") (pin "1") (pinfunction "BOOT_1") (pintype "passive"))
    )
    (net (code "67") (name "Net-(IC2-COMP)") (class "Default")
      (node (ref "C24") (pin "2") (pinfunction "2_2") (pintype "passive"))
      (node (ref "IC2") (pin "6") (pinfunction "COMP_6") (pintype "passive"))
      (node (ref "R7") (pin "2") (pinfunction "2_2") (pintype "passive"))
    )
    (net (code "68") (name "Net-(IC2-SS)") (class "Default")
      (node (ref "C23") (pin "2") (pinfunction "2_2") (pintype "passive"))
      (node (ref "IC2") (pin "4") (pinfunction "SS_4") (pintype "passive"))
    )
    (net (code "69") (name "Net-(IC2-VSENSE)") (class "Default")
      (node (ref "IC2") (pin "5") (pinfunction "VSENSE_5") (pintype "passive"))
      (node (ref "R5") (pin "1") (pinfunction "1_1") (pintype "passive"))
      (node (ref "R8") (pin "2") (pinfunction "2_2") (pintype "passive"))
    )
    (net (code "70") (name "Net-(IC4-BOOT)") (class "Default")
      (node (ref "C28") (pin "2") (pinfunction "2_2") (pintype "passive"))
      (node (ref "IC4") (pin "1") (pinfunction "BOOT_1") (pintype "passive"))
    )
    (net (code "71") (name "Net-(IC4-COMP)") (class "Default")
      (node (ref "C36") (pin "2") (pinfunction "2_2") (pintype "passive"))
      (node (ref "IC4") (pin "6") (pinfunction "COMP_6") (pintype "passive"))
      (node (ref "R17") (pin "2") (pinfunction "2_2") (pintype "passive"))
    )
    (net (code "72") (name "Net-(IC4-SS)") (class "Default")
      (node (ref "C35") (pin "2") (pinfunction "2_2") (pintype "passive"))
      (node (ref "IC4") (pin "4") (pinfunction "SS_4") (pintype "passive"))
    )
    (net (code "73") (name "Net-(IC4-VSENSE)") (class "Default")
      (node (ref "IC4") (pin "5") (pinfunction "VSENSE_5") (pintype "passive"))
      (node (ref "R14") (pin "1") (pinfunction "1_1") (pintype "passive"))
      (node (ref "R18") (pin "2") (pinfunction "2_2") (pintype "passive"))
    )
    (net (code "74") (name "Net-(J2-Pad2)") (class "Default")
      (node (ref "J2") (pin "2") (pinfunction "2_2") (pintype "passive"))
      (node (ref "R40") (pin "2") (pinfunction "2_2") (pintype "passive"))
    )
    (net (code "75") (name "Net-(J2-Pad3)") (class "Default")
      (node (ref "J2") (pin "3") (pinfunction "3_3") (pintype "passive"))
      (node (ref "R39") (pin "2") (pinfunction "2_2") (pintype "passive"))
    )
    (net (code "76") (name "Net-(P1-+)") (class "Default")
      (node (ref "P1") (pin "1") (pinfunction "+_1") (pintype "passive"))
      (node (ref "S2") (pin "2") (pinfunction "NO_2") (pintype "passive"))
    )
    (net (code "77") (name "Net-(P15-Pad2)") (class "Default")
      (node (ref "P15") (pin "2") (pinfunction "2_2") (pintype "passive"))
      (node (ref "R22") (pin "1") (pinfunction "1_1") (pintype "passive"))
    )
    (net (code "78") (name "Net-(P16-Pad2)") (class "Default")
      (node (ref "P16") (pin "2") (pinfunction "2_2") (pintype "passive"))
      (node (ref "R23") (pin "1") (pinfunction "1_1") (pintype "passive"))
    )
    (net (code "79") (name "Net-(P17-Pad2)") (class "Default")
      (node (ref "P17") (pin "2") (pinfunction "2_2") (pintype "passive"))
      (node (ref "R24") (pin "1") (pinfunction "1_1") (pintype "passive"))
    )
    (net (code "80") (name "Net-(P18-Pad2)") (class "Default")
      (node (ref "P18") (pin "2") (pinfunction "2_2") (pintype "passive"))
      (node (ref "R25") (pin "1") (pinfunction "1_1") (pintype "passive"))
    )
    (net (code "81") (name "Net-(Q1-G)") (class "Default")
      (node (ref "Q1") (pin "4") (pinfunction "G_4") (pintype "passive"))
      (node (ref "R4") (pin "1") (pinfunction "1_1") (pintype "passive"))
    )
    (net (code "82") (name "Net-(Q3-D)") (class "Default")
      (node (ref "Q3") (pin "3") (pinfunction "D_3") (pintype "passive"))
      (node (ref "R22") (pin "2") (pinfunction "2_2") (pintype "passive"))
    )
    (net (code "83") (name "Net-(Q4-D)") (class "Default")
      (node (ref "Q4") (pin "3") (pinfunction "D_3") (pintype "passive"))
      (node (ref "R23") (pin "2") (pinfunction "2_2") (pintype "passive"))
    )
    (net (code "84") (name "Net-(Q5-D)") (class "Default")
      (node (ref "Q5") (pin "3") (pinfunction "D_3") (pintype "passive"))
      (node (ref "R24") (pin "2") (pinfunction "2_2") (pintype "passive"))
    )
    (net (code "85") (name "Net-(Q6-D)") (class "Default")
      (node (ref "Q6") (pin "3") (pinfunction "D_3") (pintype "passive"))
      (node (ref "R25") (pin "2") (pinfunction "2_2") (pintype "passive"))
    )
    (net (code "86") (name "Net-(Q6-G)") (class "Default")
      (node (ref "Q6") (pin "1") (pinfunction "G_1") (pintype "passive"))
      (node (ref "R33") (pin "1") (pinfunction "1_1") (pintype "passive"))
    )
    (net (code "87") (name "Net-(R36-Pad2)") (class "Default")
      (node (ref "R36") (pin "2") (pinfunction "2_2") (pintype "passive"))
      (node (ref "R38") (pin "2") (pinfunction "2_2") (pintype "passive"))
    )
    (net (code "88") (name "Net-(S1-COMMON)") (class "Default")
      (node (ref "Q1") (pin "1") (pinfunction "S_1") (pintype "passive"))
      (node (ref "Q1") (pin "2") (pinfunction "S_2") (pintype "passive"))
      (node (ref "Q1") (pin "3") (pinfunction "S_3") (pintype "passive"))
      (node (ref "S1") (pin "1") (pinfunction "COMMON_1") (pintype "passive"))
    )
    (net (code "89") (name "Net-(S1-NO)") (class "Default")
      (node (ref "F1") (pin "2") (pinfunction "2_2") (pintype "passive"))
      (node (ref "S1") (pin "2") (pinfunction "NO_2") (pintype "passive"))
    )
    (net (code "90") (name "Net-(U2-3V3OUT)") (class "Default")
      (node (ref "C54") (pin "2") (pinfunction "2_2") (pintype "passive"))
      (node (ref "U2") (pin "17") (pinfunction "3V3OUT_17") (pintype "passive"))
    )
    (net (code "91") (name "Net-(U2-RESET#)") (class "Default")
      (node (ref "J2") (pin "1") (pinfunction "1_1") (pintype "passive"))
      (node (ref "R38") (pin "1") (pinfunction "1_1") (pintype "passive"))
      (node (ref "R41") (pin "2") (pinfunction "2_2") (pintype "passive"))
      (node (ref "U2") (pin "19") (pinfunction "RESET#_19") (pintype "passive"))
    )
    (net (code "92") (name "Net-(U2-RXD)") (class "Default")
      (node (ref "R37") (pin "2") (pinfunction "2_2") (pintype "passive"))
      (node (ref "U2") (pin "5") (pinfunction "RXD_5") (pintype "passive"))
    )
    (net (code "93") (name "Net-(U2-TXD)") (class "Default")
      (node (ref "R35") (pin "2") (pinfunction "2_2") (pintype "passive"))
      (node (ref "U2") (pin "1") (pinfunction "TXD_1") (pintype "passive"))
    )
    (net (code "94") (name "Net-(U2-USBDM)") (class "Default")
      (node (ref "R39") (pin "1") (pinfunction "1_1") (pintype "passive"))
      (node (ref "U2") (pin "16") (pinfunction "USBDM_16") (pintype "passive"))
    )
    (net (code "95") (name "Net-(U2-USBDP)") (class "Default")
      (node (ref "R40") (pin "1") (pinfunction "1_1") (pintype "passive"))
      (node (ref "U2") (pin "15") (pinfunction "USBDP_15") (pintype "passive"))
    )
    (net (code "96") (name "Net-(U2-VCC)") (class "Default")
      (node (ref "R34") (pin "1") (pinfunction "1_1") (pintype "passive"))
      (node (ref "R36") (pin "1") (pinfunction "1_1") (pintype "passive"))
      (node (ref "U2") (pin "20") (pinfunction "VCC_20") (pintype "passive"))
      (node (ref "U2") (pin "4") (pinfunction "VCCIO_4") (pintype "passive"))
    )
    (net (code "97") (name "RADAR_5V") (class "Default")
      (node (ref "C16") (pin "2") (pinfunction "2_2") (pintype "passive"))
      (node (ref "C17") (pin "2") (pinfunction "2_2") (pintype "passive"))
      (node (ref "C18") (pin "2") (pinfunction "2_2") (pintype "passive"))
      (node (ref "C19") (pin "1") (pinfunction "1_1") (pintype "passive"))
      (node (ref "C31") (pin "2") (pinfunction "2_2") (pintype "passive"))
      (node (ref "C32") (pin "2") (pinfunction "2_2") (pintype "passive"))
      (node (ref "C51") (pin "2") (pinfunction "2_2") (pintype "passive"))
      (node (ref "C52") (pin "2") (pinfunction "2_2") (pintype "passive"))
      (node (ref "CN1") (pin "1") (pinfunction "5V_1") (pintype "passive"))
      (node (ref "L1") (pin "2") (pinfunction "2_2") (pintype "passive"))
      (node (ref "P20") (pin "1") (pinfunction "1_1") (pintype "passive"))
      (node (ref "R15") (pin "2") (pinfunction "2_2") (pintype "passive"))
      (node (ref "R34") (pin "2") (pinfunction "2_2") (pintype "passive"))
      (node (ref "R5") (pin "2") (pinfunction "2_2") (pintype "passive"))
      (node (ref "R6") (pin "2") (pinfunction "2_2") (pintype "passive"))
    )
    (net (code "98") (name "USB_5V") (class "Default")
      (node (ref "C29") (pin "2") (pinfunction "2_2") (pintype "passive"))
      (node (ref "C30") (pin "2") (pinfunction "2_2") (pintype "passive"))
      (node (ref "J1") (pin "1") (pinfunction "1_1") (pintype "passive"))
      (node (ref "L2") (pin "2") (pinfunction "2_2") (pintype "passive"))
      (node (ref "R14") (pin "2") (pinfunction "2_2") (pintype "passive"))
    )
    (net (code "99") (name "VCC 5V") (class "Default")
      (node (ref "C1") (pin "1") (pinfunction "1_1") (pintype "passive"))
      (node (ref "C10") (pin "2") (pinfunction "2_2") (pintype "passive"))
      (node (ref "C11") (pin "2") (pinfunction "2_2") (pintype "passive"))
      (node (ref "C12") (pin "2") (pinfunction "2_2") (pintype "passive"))
      (node (ref "C13") (pin "2") (pinfunction "2_2") (pintype "passive"))
      (node (ref "C2") (pin "1") (pinfunction "1_1") (pintype "passive"))
      (node (ref "C3") (pin "1") (pinfunction "1_1") (pintype "passive"))
      (node (ref "C4") (pin "1") (pinfunction "1_1") (pintype "passive"))
      (node (ref "C6") (pin "2") (pinfunction "2_2") (pintype "passive"))
      (node (ref "C7") (pin "2") (pinfunction "2_2") (pintype "passive"))
      (node (ref "C8") (pin "2") (pinfunction "2_2") (pintype "passive"))
      (node (ref "C9") (pin "2") (pinfunction "2_2") (pintype "passive"))
      (node (ref "MP1584") (pin "5") (pinfunction "OUT+_5") (pintype "passive"))
      (node (ref "MP1584") (pin "6") (pinfunction "OUT+_6") (pintype "passive"))
      (node (ref "P10") (pin "1") (pinfunction "5V_1") (pintype "passive"))
      (node (ref "P11") (pin "1") (pinfunction "5V_1") (pintype "passive"))
      (node (ref "P15") (pin "1") (pinfunction "1_1") (pintype "passive"))
      (node (ref "P16") (pin "1") (pinfunction "1_1") (pintype "passive"))
      (node (ref "P17") (pin "1") (pinfunction "1_1") (pintype "passive"))
      (node (ref "P18") (pin "1") (pinfunction "1_1") (pintype "passive"))
      (node (ref "P3") (pin "1") (pinfunction "5V_1") (pintype "passive"))
      (node (ref "P3") (pin "2") (pinfunction "5V_2") (pintype "passive"))
      (node (ref "P4") (pin "1") (pinfunction "5V_1") (pintype "passive"))
      (node (ref "P4") (pin "2") (pinfunction "5V_2") (pintype "passive"))
      (node (ref "P5") (pin "2") (pinfunction "5V_2") (pintype "passive"))
      (node (ref "P6") (pin "2") (pinfunction "5V_2") (pintype "passive"))
      (node (ref "P7") (pin "2") (pinfunction "5V_2") (pintype "passive"))
      (node (ref "P8") (pin "2") (pinfunction "5V_2") (pintype "passive"))
      (node (ref "P9") (pin "2") (pinfunction "5V_2") (pintype "passive"))
    )
    (net (code "100") (name "VCC 7.4V") (class "Default")
      (node (ref "MP1584") (pin "3") (pinfunction "IN+_3") (pintype "passive"))
      (node (ref "MP1584") (pin "4") (pinfunction "IN+_4") (pintype "passive"))
      (node (ref "R2") (pin "2") (pinfunction "2_2") (pintype "passive"))
      (node (ref "S2") (pin "1") (pinfunction "COMMON_1") (pintype "passive"))
    )
    (net (code "101") (name "VIN") (class "Default")
      (node (ref "D1") (pin "2") (pinfunction "K_2") (pintype "passive"))
      (node (ref "F1") (pin "1") (pinfunction "1_1") (pintype "passive"))
      (node (ref "P2") (pin "1") (pinfunction "+_1") (pintype "passive"))
    )
    (net (code "102") (name "unconnected-(IC2-EN-Pad3)") (class "Default")
      (node (ref "IC2") (pin "3") (pinfunction "EN_3") (pintype "passive"))
    )
    (net (code "103") (name "unconnected-(IC4-EN-Pad3)") (class "Default")
      (node (ref "IC4") (pin "3") (pinfunction "EN_3") (pintype "passive"))
    )
    (net (code "104") (name "unconnected-(J1-Pad2)") (class "Default")
      (node (ref "J1") (pin "2") (pinfunction "2_2") (pintype "passive"))
    )
    (net (code "105") (name "unconnected-(J1-Pad3)") (class "Default")
      (node (ref "J1") (pin "3") (pinfunction "3_3") (pintype "passive"))
    )
    (net (code "106") (name "unconnected-(J1-PadMH1)") (class "Default")
      (node (ref "J1") (pin "MH1") (pinfunction "MH1_MH1") (pintype "passive"))
    )
    (net (code "107") (name "unconnected-(J1-PadMH2)") (class "Default")
      (node (ref "J1") (pin "MH2") (pinfunction "MH2_MH2") (pintype "passive"))
    )
    (net (code "108") (name "unconnected-(J2-PadMH1)") (class "Default")
      (node (ref "J2") (pin "MH1") (pinfunction "MH1_MH1") (pintype "passive"))
    )
    (net (code "109") (name "unconnected-(J2-PadMH2)") (class "Default")
      (node (ref "J2") (pin "MH2") (pinfunction "MH2_MH2") (pintype "passive"))
    )
    (net (code "110") (name "unconnected-(P12-NO-Pad3)") (class "Default")
      (node (ref "P12") (pin "3") (pinfunction "NO_3") (pintype "passive"))
    )
    (net (code "111") (name "unconnected-(P12-NO-Pad8)") (class "Default")
      (node (ref "P12") (pin "8") (pinfunction "NO_8") (pintype "passive"))
    )
    (net (code "112") (name "unconnected-(P12-NO-Pad9)") (class "Default")
      (node (ref "P12") (pin "9") (pinfunction "NO_9") (pintype "passive"))
    )
    (net (code "113") (name "unconnected-(S1-Pad3)") (class "Default")
      (node (ref "S1") (pin "3") (pinfunction "3_3") (pintype "passive"))
    )
    (net (code "114") (name "unconnected-(S2-Pad3)") (class "Default")
      (node (ref "S2") (pin "3") (pinfunction "3_3") (pintype "passive"))
    )
    (net (code "115") (name "unconnected-(U2-CBUS0-Pad23)") (class "Default")
      (node (ref "U2") (pin "23") (pinfunction "CBUS0_23") (pintype "passive"))
    )
    (net (code "116") (name "unconnected-(U2-CBUS1-Pad22)") (class "Default")
      (node (ref "U2") (pin "22") (pinfunction "CBUS1_22") (pintype "passive"))
    )
    (net (code "117") (name "unconnected-(U2-CBUS2-Pad13)") (class "Default")
      (node (ref "U2") (pin "13") (pinfunction "CBUS2_13") (pintype "passive"))
    )
    (net (code "118") (name "unconnected-(U2-CBUS3-Pad14)") (class "Default")
      (node (ref "U2") (pin "14") (pinfunction "CBUS3_14") (pintype "passive"))
    )
    (net (code "119") (name "unconnected-(U2-CBUS4-Pad12)") (class "Default")
      (node (ref "U2") (pin "12") (pinfunction "CBUS4_12") (pintype "passive"))
    )
    (net (code "120") (name "unconnected-(U2-CTS#-Pad11)") (class "Default")
      (node (ref "U2") (pin "11") (pinfunction "CTS#_11") (pintype "passive"))
    )
    (net (code "121") (name "unconnected-(U2-DCD#-Pad10)") (class "Default")
      (node (ref "U2") (pin "10") (pinfunction "DCD#_10") (pintype "passive"))
    )
    (net (code "122") (name "unconnected-(U2-DSR#-Pad9)") (class "Default")
      (node (ref "U2") (pin "9") (pinfunction "DSR#_9") (pintype "passive"))
    )
    (net (code "123") (name "unconnected-(U2-DTR#-Pad2)") (class "Default")
      (node (ref "U2") (pin "2") (pinfunction "DTR#_2") (pintype "passive"))
    )
    (net (code "124") (name "unconnected-(U2-NC_1-Pad8)") (class "Default")
      (node (ref "U2") (pin "8") (pinfunction "NC_1_8") (pintype "passive"))
    )
    (net (code "125") (name "unconnected-(U2-NC_2-Pad24)") (class "Default")
      (node (ref "U2") (pin "24") (pinfunction "NC_2_24") (pintype "passive"))
    )
    (net (code "126") (name "unconnected-(U2-RI#-Pad6)") (class "Default")
      (node (ref "U2") (pin "6") (pinfunction "RI#_6") (pintype "passive"))
    )
    (net (code "127") (name "unconnected-(U2-RTS#-Pad3)") (class "Default")
      (node (ref "U2") (pin "3") (pinfunction "RTS#_3") (pintype "passive"))
    )
  )
)
